# CAN_Breakout.net
KiCad netlist of a schematic drawn in Altium Designer
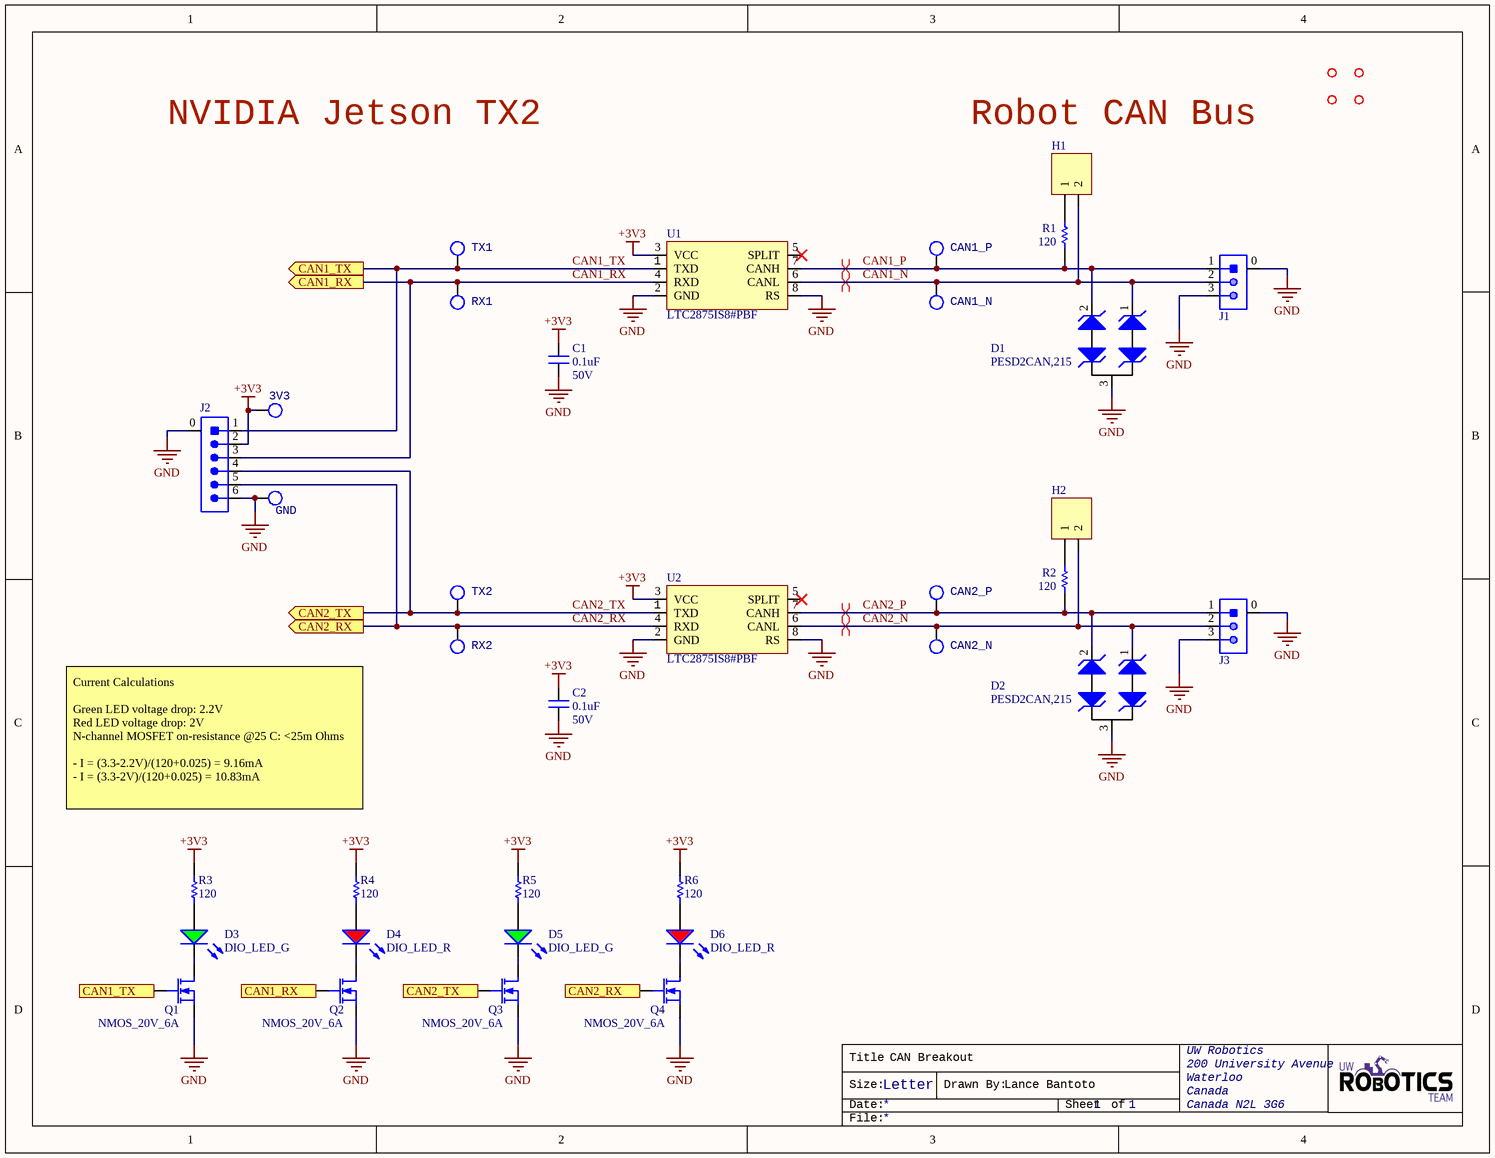
[diagram p0: CAN Breakout.SchDoc]

(export (version "E")
  (design (tool "Eeschema 10.0.6"))
  (components
    (comp (ref "3V3")
      (value "TESTPOINT_LOOP")
      (footprint "TESTPOINT_LOOP")
      (description "Loop testpoint through-hole pad")
      (libsource (lib "UWRT_Schematic_Library_2020") (part "TESTPOINT_LOOP"))
    )
    (comp (ref "C1")
      (value "0.1uF")
      (footprint "CAPC2012X140N")
      (description "CAP CER 0.1UF 50V X7R 0805")
      (fields
        (field (name "VOLTAGE RATING") "50V")
        (field (name "TOLERANCE") "10%")
        (field (name "Comment") "CAP_0.1uF_50V_0805")
      )
      (libsource (lib "UWRT_Schematic_Library_2020") (part "CAP_0.1uF_50V_0805"))
    )
    (comp (ref "C2")
      (value "0.1uF")
      (footprint "CAPC2012X140N")
      (description "CAP CER 0.1UF 50V X7R 0805")
      (fields
        (field (name "VOLTAGE RATING") "50V")
        (field (name "TOLERANCE") "10%")
        (field (name "Comment") "CAP_0.1uF_50V_0805")
      )
      (libsource (lib "UWRT_Schematic_Library_2020") (part "CAP_0.1uF_50V_0805"))
    )
    (comp (ref "CAN1_N")
      (value "TESTPOINT_LOOP")
      (footprint "TESTPOINT_LOOP")
      (description "Loop testpoint through-hole pad")
      (libsource (lib "UWRT_Schematic_Library_2020") (part "TESTPOINT_LOOP"))
    )
    (comp (ref "CAN1_P")
      (value "TESTPOINT_LOOP")
      (footprint "TESTPOINT_LOOP")
      (description "Loop testpoint through-hole pad")
      (libsource (lib "UWRT_Schematic_Library_2020") (part "TESTPOINT_LOOP"))
    )
    (comp (ref "CAN2_N")
      (value "TESTPOINT_LOOP")
      (footprint "TESTPOINT_LOOP")
      (description "Loop testpoint through-hole pad")
      (libsource (lib "UWRT_Schematic_Library_2020") (part "TESTPOINT_LOOP"))
    )
    (comp (ref "CAN2_P")
      (value "TESTPOINT_LOOP")
      (footprint "TESTPOINT_LOOP")
      (description "Loop testpoint through-hole pad")
      (libsource (lib "UWRT_Schematic_Library_2020") (part "TESTPOINT_LOOP"))
    )
    (comp (ref "D1")
      (value "TVS_DIODE_CAN")
      (footprint "TVS_DIODE_CAN")
      (description "TVS DIODE 24V 41V SOT323-3")
      (fields (field (name "MANUFACTURER PART NUMBER 1") "PESD2CAN,215"))
      (libsource (lib "UWRT_Schematic_Library_2020") (part "TVS_DIODE_CAN"))
    )
    (comp (ref "D2")
      (value "TVS_DIODE_CAN")
      (footprint "TVS_DIODE_CAN")
      (description "TVS DIODE 24V 41V SOT323-3")
      (fields (field (name "MANUFACTURER PART NUMBER 1") "PESD2CAN,215"))
      (libsource (lib "UWRT_Schematic_Library_2020") (part "TVS_DIODE_CAN"))
    )
    (comp (ref "D3")
      (value "DIO_LED_G")
      (footprint "LED_0805_LINE")
      (description "LED GREEN DIFFUSED 0805 SMD")
      (libsource (lib "UWRT_Schematic_Library_2020") (part "DIO_LED_G"))
    )
    (comp (ref "D4")
      (value "DIO_LED_R")
      (footprint "LED_0805_LINE")
      (description "LED RED DIFFUSED 0805 SMD")
      (libsource (lib "UWRT_Schematic_Library_2020") (part "DIO_LED_R"))
    )
    (comp (ref "D5")
      (value "DIO_LED_G")
      (footprint "LED_0805_LINE")
      (description "LED GREEN DIFFUSED 0805 SMD")
      (libsource (lib "UWRT_Schematic_Library_2020") (part "DIO_LED_G"))
    )
    (comp (ref "D6")
      (value "DIO_LED_R")
      (footprint "LED_0805_LINE")
      (description "LED RED DIFFUSED 0805 SMD")
      (libsource (lib "UWRT_Schematic_Library_2020") (part "DIO_LED_R"))
    )
    (comp (ref "GND")
      (value "TESTPOINT_LOOP")
      (footprint "TESTPOINT_LOOP")
      (description "Loop testpoint through-hole pad")
      (libsource (lib "UWRT_Schematic_Library_2020") (part "TESTPOINT_LOOP"))
    )
    (comp (ref "H1")
      (value "JUMPER_2")
      (footprint "HDR1X2")
      (description "HEADER 2X1")
      (libsource (lib "UWRT_Schematic_Library_2020") (part "JUMPER_2"))
    )
    (comp (ref "H2")
      (value "JUMPER_2")
      (footprint "HDR1X2")
      (description "HEADER 2X1")
      (libsource (lib "UWRT_Schematic_Library_2020") (part "JUMPER_2"))
    )
    (comp (ref "J1")
      (value "CON_3M_SM4")
      (footprint "JST-B3B-SM4-TB")
      (description "CONN HEADER SMD 3POS 2MM")
      (libsource (lib "UWRT_Schematic_Library_2020") (part "CON_3M_SM4"))
    )
    (comp (ref "J2")
      (value "CON_6M_SM4")
      (footprint "JST-B6B-SM4-TB")
      (description "CONN HEADER SMD 6POS 2MM")
      (fields
        (field (name "MANUFACTURER PART NUMBER") "B6B-PH-SM4-TB(LF)(SN)")
        (field (name "MANUFACTURER") "JST")
      )
      (libsource (lib "UWRT_Schematic_Library_2020") (part "CON_6M_SM4"))
    )
    (comp (ref "J3")
      (value "CON_3M_SM4")
      (footprint "JST-B3B-SM4-TB")
      (description "CONN HEADER SMD 3POS 2MM")
      (libsource (lib "UWRT_Schematic_Library_2020") (part "CON_3M_SM4"))
    )
    (comp (ref "MH1")
      (value "MOUNTING_HOLES")
      (footprint "MOUNTING_HOLE")
      (description "6cm x 6cm")
      (libsource (lib "UWRT_Schematic_Library_2020") (part "MOUNTING_HOLES"))
    )
    (comp (ref "MH2")
      (value "MOUNTING_HOLES")
      (footprint "MOUNTING_HOLE")
      (description "6cm x 6cm")
      (libsource (lib "UWRT_Schematic_Library_2020") (part "MOUNTING_HOLES"))
    )
    (comp (ref "MH3")
      (value "MOUNTING_HOLES")
      (footprint "MOUNTING_HOLE")
      (description "6cm x 6cm")
      (libsource (lib "UWRT_Schematic_Library_2020") (part "MOUNTING_HOLES"))
    )
    (comp (ref "MH4")
      (value "MOUNTING_HOLES")
      (footprint "MOUNTING_HOLE")
      (description "6cm x 6cm")
      (libsource (lib "UWRT_Schematic_Library_2020") (part "MOUNTING_HOLES"))
    )
    (comp (ref "Q1")
      (value "NMOS_20V_6A")
      (footprint "NMOS_SOT23-3")
      (description "MOSFET N-CH 20V 6A SOT23")
      (libsource (lib "UWRT_Schematic_Library_2020") (part "NMOS_20V_6A"))
    )
    (comp (ref "Q2")
      (value "NMOS_20V_6A")
      (footprint "NMOS_SOT23-3")
      (description "MOSFET N-CH 20V 6A SOT23")
      (libsource (lib "UWRT_Schematic_Library_2020") (part "NMOS_20V_6A"))
    )
    (comp (ref "Q3")
      (value "NMOS_20V_6A")
      (footprint "NMOS_SOT23-3")
      (description "MOSFET N-CH 20V 6A SOT23")
      (libsource (lib "UWRT_Schematic_Library_2020") (part "NMOS_20V_6A"))
    )
    (comp (ref "Q4")
      (value "NMOS_20V_6A")
      (footprint "NMOS_SOT23-3")
      (description "MOSFET N-CH 20V 6A SOT23")
      (libsource (lib "UWRT_Schematic_Library_2020") (part "NMOS_20V_6A"))
    )
    (comp (ref "R1")
      (value "120")
      (footprint "RESC2012X60N")
      (description "RES SMD 120 OHM 1% 1/8W 0805")
      (fields (field (name "RESISTANCE") "120"))
      (libsource (lib "UWRT_Schematic_Library_2020") (part "RES_120R_0805"))
    )
    (comp (ref "R2")
      (value "120")
      (footprint "RESC2012X60N")
      (description "RES SMD 120 OHM 1% 1/8W 0805")
      (fields (field (name "RESISTANCE") "120"))
      (libsource (lib "UWRT_Schematic_Library_2020") (part "RES_120R_0805"))
    )
    (comp (ref "R3")
      (value "120")
      (footprint "RESC2012X60N")
      (description "RES SMD 120 OHM 1% 1/8W 0805")
      (fields (field (name "RESISTANCE") "120"))
      (libsource (lib "UWRT_Schematic_Library_2020") (part "RES_120R_0805"))
    )
    (comp (ref "R4")
      (value "120")
      (footprint "RESC2012X60N")
      (description "RES SMD 120 OHM 1% 1/8W 0805")
      (fields (field (name "RESISTANCE") "120"))
      (libsource (lib "UWRT_Schematic_Library_2020") (part "RES_120R_0805"))
    )
    (comp (ref "R5")
      (value "120")
      (footprint "RESC2012X60N")
      (description "RES SMD 120 OHM 1% 1/8W 0805")
      (fields (field (name "RESISTANCE") "120"))
      (libsource (lib "UWRT_Schematic_Library_2020") (part "RES_120R_0805"))
    )
    (comp (ref "R6")
      (value "120")
      (footprint "RESC2012X60N")
      (description "RES SMD 120 OHM 1% 1/8W 0805")
      (fields (field (name "RESISTANCE") "120"))
      (libsource (lib "UWRT_Schematic_Library_2020") (part "RES_120R_0805"))
    )
    (comp (ref "RX1")
      (value "TESTPOINT_LOOP")
      (footprint "TESTPOINT_LOOP")
      (description "Loop testpoint through-hole pad")
      (libsource (lib "UWRT_Schematic_Library_2020") (part "TESTPOINT_LOOP"))
    )
    (comp (ref "RX2")
      (value "TESTPOINT_LOOP")
      (footprint "TESTPOINT_LOOP")
      (description "Loop testpoint through-hole pad")
      (libsource (lib "UWRT_Schematic_Library_2020") (part "TESTPOINT_LOOP"))
    )
    (comp (ref "TX1")
      (value "TESTPOINT_LOOP")
      (footprint "TESTPOINT_LOOP")
      (description "Loop testpoint through-hole pad")
      (libsource (lib "UWRT_Schematic_Library_2020") (part "TESTPOINT_LOOP"))
    )
    (comp (ref "TX2")
      (value "TESTPOINT_LOOP")
      (footprint "TESTPOINT_LOOP")
      (description "Loop testpoint through-hole pad")
      (libsource (lib "UWRT_Schematic_Library_2020") (part "TESTPOINT_LOOP"))
    )
    (comp (ref "U1")
      (value "IC TXRX CAN")
      (footprint "LT-S8_N")
      (description "IC TXRX CAN 4MBPS 8SO")
      (fields (field (name "MANUFACTURER PART NUMBER 1") "LTC2875IS8#PBF"))
      (libsource (lib "UWRT_Schematic_Library_2020") (part "LTC2875"))
    )
    (comp (ref "U2")
      (value "IC TXRX CAN")
      (footprint "LT-S8_N")
      (description "IC TXRX CAN 4MBPS 8SO")
      (fields (field (name "MANUFACTURER PART NUMBER 1") "LTC2875IS8#PBF"))
      (libsource (lib "UWRT_Schematic_Library_2020") (part "LTC2875"))
    )
  )
  (nets
    (net (code "1") (name "+3V3") (class "Default")
      (node (ref "3V3") (pin "1") (pintype "passive"))
      (node (ref "C1") (pin "2") (pinfunction "2_2") (pintype "passive"))
      (node (ref "C2") (pin "2") (pinfunction "2_2") (pintype "passive"))
      (node (ref "J2") (pin "2") (pinfunction "2_2") (pintype "passive"))
      (node (ref "R3") (pin "2") (pinfunction "2_2") (pintype "passive"))
      (node (ref "R4") (pin "2") (pinfunction "2_2") (pintype "passive"))
      (node (ref "R5") (pin "2") (pinfunction "2_2") (pintype "passive"))
      (node (ref "R6") (pin "2") (pinfunction "2_2") (pintype "passive"))
      (node (ref "U1") (pin "3") (pinfunction "VCC_3") (pintype "passive"))
      (node (ref "U2") (pin "3") (pinfunction "VCC_3") (pintype "passive"))
    )
    (net (code "2") (name "/CAN1_N") (class "Default")
      (node (ref "CAN1_N") (pin "1") (pintype "passive"))
      (node (ref "D1") (pin "1") (pinfunction "1_1") (pintype "passive"))
      (node (ref "H1") (pin "2") (pinfunction "2_2") (pintype "passive"))
      (node (ref "J1") (pin "2") (pinfunction "2_2") (pintype "passive"))
      (node (ref "U1") (pin "6") (pinfunction "CANL_6") (pintype "passive"))
    )
    (net (code "3") (name "/CAN1_P") (class "Default")
      (node (ref "CAN1_P") (pin "1") (pintype "passive"))
      (node (ref "D1") (pin "2") (pinfunction "2_2") (pintype "passive"))
      (node (ref "J1") (pin "1") (pinfunction "1_1") (pintype "passive"))
      (node (ref "R1") (pin "1") (pinfunction "1_1") (pintype "passive"))
      (node (ref "U1") (pin "7") (pinfunction "CANH_7") (pintype "passive"))
    )
    (net (code "4") (name "/CAN1_RX") (class "Default")
      (node (ref "J2") (pin "3") (pinfunction "3_3") (pintype "passive"))
      (node (ref "Q2") (pin "1") (pinfunction "G_1") (pintype "passive"))
      (node (ref "RX1") (pin "1") (pintype "passive"))
      (node (ref "U1") (pin "4") (pinfunction "RXD_4") (pintype "passive"))
    )
    (net (code "5") (name "/CAN1_TX") (class "Default")
      (node (ref "J2") (pin "1") (pinfunction "1_1") (pintype "passive"))
      (node (ref "Q1") (pin "1") (pinfunction "G_1") (pintype "passive"))
      (node (ref "TX1") (pin "1") (pintype "passive"))
      (node (ref "U1") (pin "1") (pinfunction "TXD_1") (pintype "passive"))
    )
    (net (code "6") (name "/CAN2_N") (class "Default")
      (node (ref "CAN2_N") (pin "1") (pintype "passive"))
      (node (ref "D2") (pin "1") (pinfunction "1_1") (pintype "passive"))
      (node (ref "H2") (pin "2") (pinfunction "2_2") (pintype "passive"))
      (node (ref "J3") (pin "2") (pinfunction "2_2") (pintype "passive"))
      (node (ref "U2") (pin "6") (pinfunction "CANL_6") (pintype "passive"))
    )
    (net (code "7") (name "/CAN2_P") (class "Default")
      (node (ref "CAN2_P") (pin "1") (pintype "passive"))
      (node (ref "D2") (pin "2") (pinfunction "2_2") (pintype "passive"))
      (node (ref "J3") (pin "1") (pinfunction "1_1") (pintype "passive"))
      (node (ref "R2") (pin "1") (pinfunction "1_1") (pintype "passive"))
      (node (ref "U2") (pin "7") (pinfunction "CANH_7") (pintype "passive"))
    )
    (net (code "8") (name "/CAN2_RX") (class "Default")
      (node (ref "J2") (pin "5") (pinfunction "5_5") (pintype "passive"))
      (node (ref "Q4") (pin "1") (pinfunction "G_1") (pintype "passive"))
      (node (ref "RX2") (pin "1") (pintype "passive"))
      (node (ref "U2") (pin "4") (pinfunction "RXD_4") (pintype "passive"))
    )
    (net (code "9") (name "/CAN2_TX") (class "Default")
      (node (ref "J2") (pin "4") (pinfunction "4_4") (pintype "passive"))
      (node (ref "Q3") (pin "1") (pinfunction "G_1") (pintype "passive"))
      (node (ref "TX2") (pin "1") (pintype "passive"))
      (node (ref "U2") (pin "1") (pinfunction "TXD_1") (pintype "passive"))
    )
    (net (code "10") (name "GND") (class "Default")
      (node (ref "C1") (pin "1") (pinfunction "1_1") (pintype "passive"))
      (node (ref "C2") (pin "1") (pinfunction "1_1") (pintype "passive"))
      (node (ref "D1") (pin "3") (pinfunction "3_3") (pintype "passive"))
      (node (ref "D2") (pin "3") (pinfunction "3_3") (pintype "passive"))
      (node (ref "GND") (pin "1") (pintype "passive"))
      (node (ref "J1") (pin "0") (pinfunction "0_0") (pintype "passive"))
      (node (ref "J1") (pin "3") (pinfunction "3_3") (pintype "passive"))
      (node (ref "J2") (pin "0") (pinfunction "0_0") (pintype "passive"))
      (node (ref "J2") (pin "6") (pinfunction "6_6") (pintype "passive"))
      (node (ref "J3") (pin "0") (pinfunction "0_0") (pintype "passive"))
      (node (ref "J3") (pin "3") (pinfunction "3_3") (pintype "passive"))
      (node (ref "Q1") (pin "2") (pinfunction "S_2") (pintype "passive"))
      (node (ref "Q2") (pin "2") (pinfunction "S_2") (pintype "passive"))
      (node (ref "Q3") (pin "2") (pinfunction "S_2") (pintype "passive"))
      (node (ref "Q4") (pin "2") (pinfunction "S_2") (pintype "passive"))
      (node (ref "U1") (pin "2") (pinfunction "GND_2") (pintype "passive"))
      (node (ref "U1") (pin "8") (pinfunction "RS_8") (pintype "passive"))
      (node (ref "U2") (pin "2") (pinfunction "GND_2") (pintype "passive"))
      (node (ref "U2") (pin "8") (pinfunction "RS_8") (pintype "passive"))
    )
    (net (code "11") (name "Net-(D3-A)") (class "Default")
      (node (ref "D3") (pin "1") (pinfunction "A_1") (pintype "passive"))
      (node (ref "R3") (pin "1") (pinfunction "1_1") (pintype "passive"))
    )
    (net (code "12") (name "Net-(D3-K)") (class "Default")
      (node (ref "D3") (pin "2") (pinfunction "K_2") (pintype "passive"))
      (node (ref "Q1") (pin "3") (pinfunction "D_3") (pintype "passive"))
    )
    (net (code "13") (name "Net-(D4-A)") (class "Default")
      (node (ref "D4") (pin "1") (pinfunction "A_1") (pintype "passive"))
      (node (ref "R4") (pin "1") (pinfunction "1_1") (pintype "passive"))
    )
    (net (code "14") (name "Net-(D4-K)") (class "Default")
      (node (ref "D4") (pin "2") (pinfunction "K_2") (pintype "passive"))
      (node (ref "Q2") (pin "3") (pinfunction "D_3") (pintype "passive"))
    )
    (net (code "15") (name "Net-(D5-A)") (class "Default")
      (node (ref "D5") (pin "1") (pinfunction "A_1") (pintype "passive"))
      (node (ref "R5") (pin "1") (pinfunction "1_1") (pintype "passive"))
    )
    (net (code "16") (name "Net-(D5-K)") (class "Default")
      (node (ref "D5") (pin "2") (pinfunction "K_2") (pintype "passive"))
      (node (ref "Q3") (pin "3") (pinfunction "D_3") (pintype "passive"))
    )
    (net (code "17") (name "Net-(D6-A)") (class "Default")
      (node (ref "D6") (pin "1") (pinfunction "A_1") (pintype "passive"))
      (node (ref "R6") (pin "1") (pinfunction "1_1") (pintype "passive"))
    )
    (net (code "18") (name "Net-(D6-K)") (class "Default")
      (node (ref "D6") (pin "2") (pinfunction "K_2") (pintype "passive"))
      (node (ref "Q4") (pin "3") (pinfunction "D_3") (pintype "passive"))
    )
    (net (code "19") (name "Net-(H1-Pad1)") (class "Default")
      (node (ref "H1") (pin "1") (pinfunction "1_1") (pintype "passive"))
      (node (ref "R1") (pin "2") (pinfunction "2_2") (pintype "passive"))
    )
    (net (code "20") (name "Net-(H2-Pad1)") (class "Default")
      (node (ref "H2") (pin "1") (pinfunction "1_1") (pintype "passive"))
      (node (ref "R2") (pin "2") (pinfunction "2_2") (pintype "passive"))
    )
    (net (code "21") (name "unconnected-(U1-SPLIT-Pad5)") (class "Default")
      (node (ref "U1") (pin "5") (pinfunction "SPLIT_5") (pintype "passive+no_connect"))
    )
    (net (code "22") (name "unconnected-(U2-SPLIT-Pad5)") (class "Default")
      (node (ref "U2") (pin "5") (pinfunction "SPLIT_5") (pintype "passive+no_connect"))
    )
  )
)
